# 04_ADC.net
KiCad netlist of a schematic drawn in Altium Designer
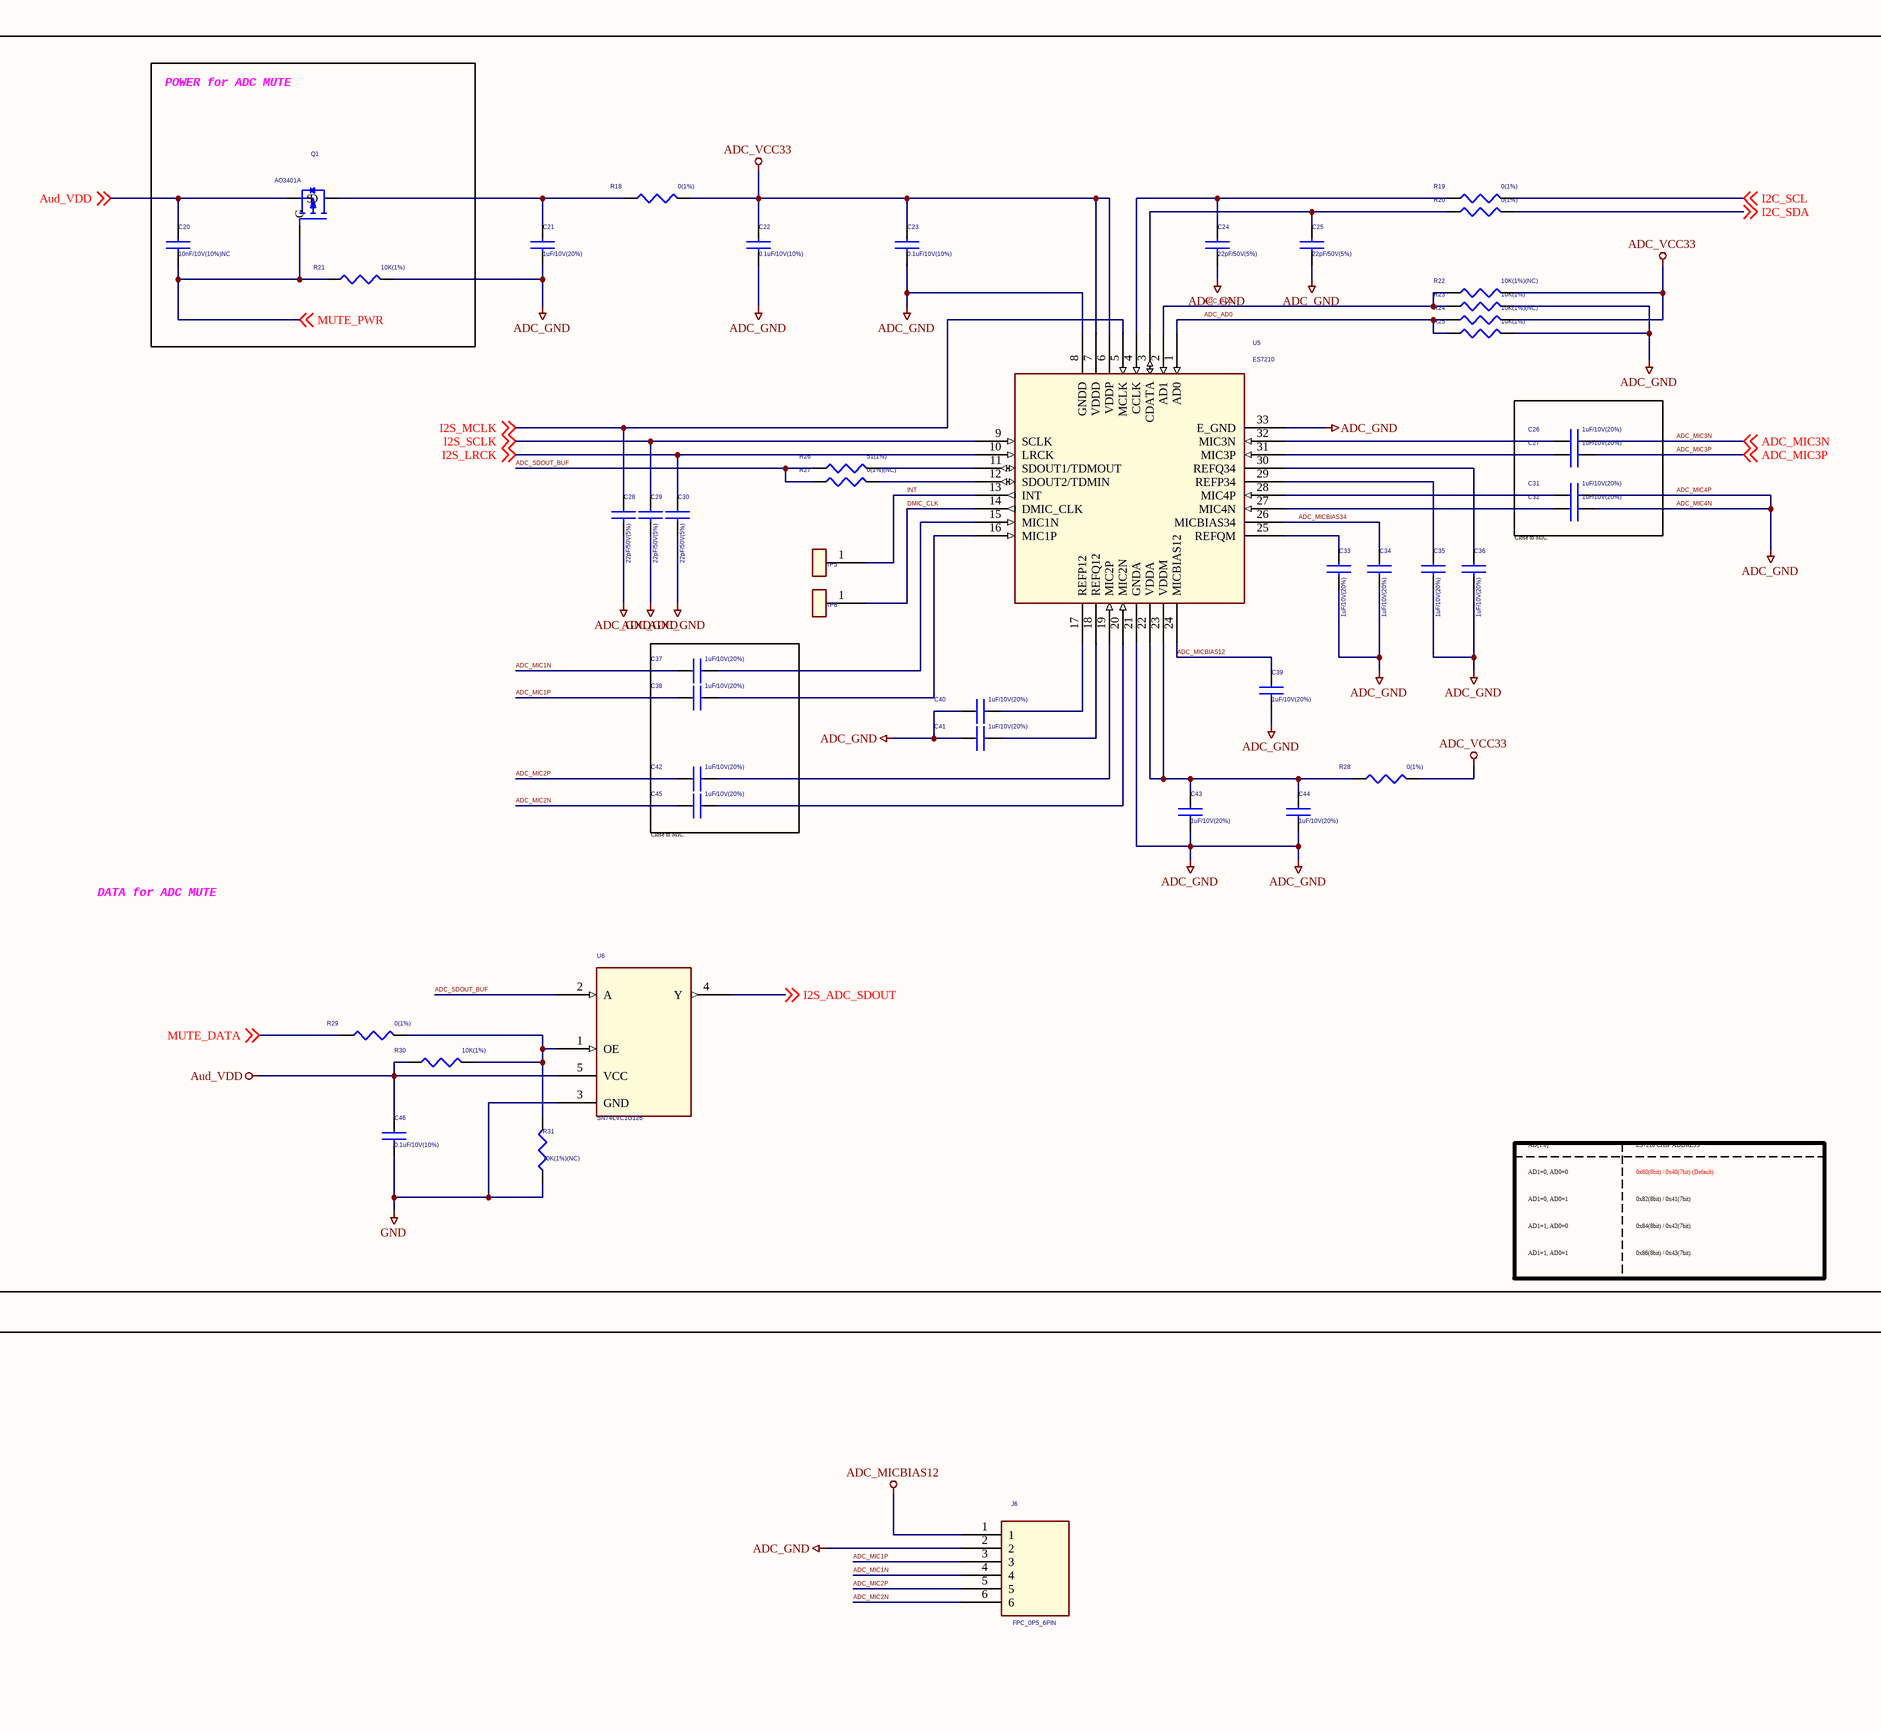
[diagram p0: 04_ADC.SchDoc, left]
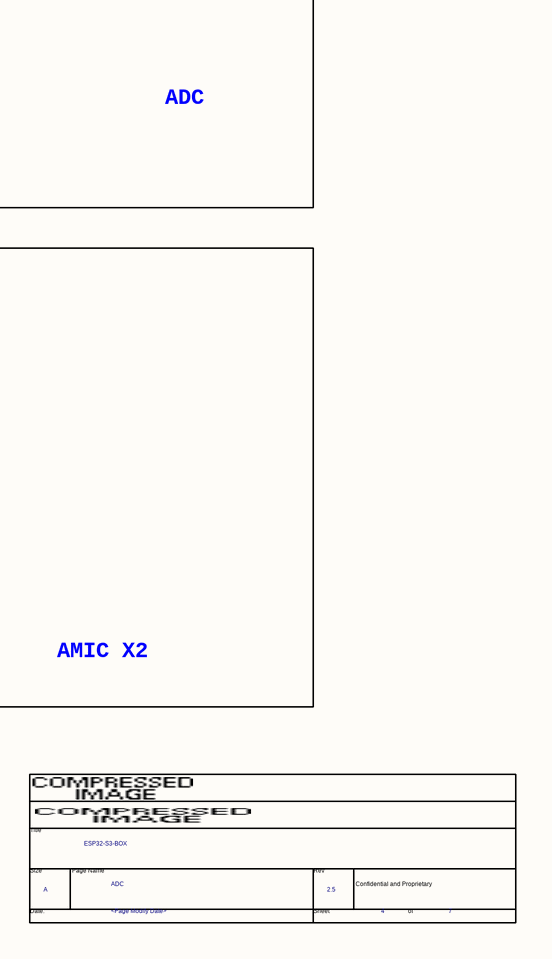
[diagram p1: 04_ADC.SchDoc, right]

(export (version "E")
  (design (tool "Eeschema 10.0.6"))
  (components
    (comp (ref "*")
      (value "espTitleBlock3")
      (fields
        (field (name "PAGE MODIFY DATE") "<Page Modify Date>")
        (field (name "PAGE NAME") "ADC")
        (field (name "TITLE") "ESP32-S3-BOX")
        (field (name "PAGE SIZE") "A")
        (field (name "PAGE NUMBER") "4")
        (field (name "PAGE COUNT") "7")
        (field (name "REVCODE") "2.5")
      )
      (libsource (lib "*") (part "espTitleBlock3"))
    )
    (comp (ref "C20")
      (value "10nF/10V(10%)NC")
      (footprint "C0201")
      (fields (field (name "PART NUMBER") "ES11024103600000"))
      (libsource (lib "*") (part "CAPACITOR"))
    )
    (comp (ref "C21")
      (value "1uF/10V(20%)")
      (footprint "C0201")
      (fields (field (name "PART NUMBER") "ES11026103700001"))
      (libsource (lib "*") (part "CAPACITOR"))
    )
    (comp (ref "C22")
      (value "0.1uF/10V(10%)")
      (footprint "C0201")
      (fields (field (name "PART NUMBER") "ES11025103610001"))
      (libsource (lib "*") (part "CAPACITOR"))
    )
    (comp (ref "C23")
      (value "0.1uF/10V(10%)")
      (footprint "C0201")
      (fields (field (name "PART NUMBER") "ES11025103610001"))
      (libsource (lib "*") (part "CAPACITOR"))
    )
    (comp (ref "C24")
      (value "22pF/50V(5%)")
      (footprint "C0201")
      (fields (field (name "PART NUMBER") "ES11021226520000"))
      (libsource (lib "*") (part "CAPACITOR"))
    )
    (comp (ref "C25")
      (value "22pF/50V(5%)")
      (footprint "C0201")
      (fields (field (name "PART NUMBER") "ES11021226520000"))
      (libsource (lib "*") (part "CAPACITOR"))
    )
    (comp (ref "C26")
      (value "1uF/10V(20%)")
      (footprint "C0201")
      (fields (field (name "PART NUMBER") "ES11026103700001"))
      (libsource (lib "*") (part "CAPACITOR"))
    )
    (comp (ref "C27")
      (value "1uF/10V(20%)")
      (footprint "C0201")
      (fields (field (name "PART NUMBER") "ES11026103700001"))
      (libsource (lib "*") (part "CAPACITOR"))
    )
    (comp (ref "C28")
      (value "22pF/50V(5%)")
      (footprint "C0201")
      (fields (field (name "PART NUMBER") "ES11021226520000"))
      (libsource (lib "*") (part "CAPACITOR"))
    )
    (comp (ref "C29")
      (value "22pF/50V(5%)")
      (footprint "C0201")
      (fields (field (name "PART NUMBER") "ES11021226520000"))
      (libsource (lib "*") (part "CAPACITOR"))
    )
    (comp (ref "C30")
      (value "22pF/50V(5%)")
      (footprint "C0201")
      (fields (field (name "PART NUMBER") "ES11021226520000"))
      (libsource (lib "*") (part "CAPACITOR"))
    )
    (comp (ref "C31")
      (value "1uF/10V(20%)")
      (footprint "C0201")
      (fields (field (name "PART NUMBER") "ES11026103700001"))
      (libsource (lib "*") (part "CAPACITOR"))
    )
    (comp (ref "C32")
      (value "1uF/10V(20%)")
      (footprint "C0201")
      (fields (field (name "PART NUMBER") "ES11026103700001"))
      (libsource (lib "*") (part "CAPACITOR"))
    )
    (comp (ref "C33")
      (value "1uF/10V(20%)")
      (footprint "C0201")
      (fields (field (name "PART NUMBER") "ES11026103700001"))
      (libsource (lib "*") (part "CAPACITOR"))
    )
    (comp (ref "C34")
      (value "1uF/10V(20%)")
      (footprint "C0201")
      (fields (field (name "PART NUMBER") "ES11026103700001"))
      (libsource (lib "*") (part "CAPACITOR"))
    )
    (comp (ref "C35")
      (value "1uF/10V(20%)")
      (footprint "C0201")
      (fields (field (name "PART NUMBER") "ES11026103700001"))
      (libsource (lib "*") (part "CAPACITOR"))
    )
    (comp (ref "C36")
      (value "1uF/10V(20%)")
      (footprint "C0201")
      (fields (field (name "PART NUMBER") "ES11026103700001"))
      (libsource (lib "*") (part "CAPACITOR"))
    )
    (comp (ref "C37")
      (value "1uF/10V(20%)")
      (footprint "C0201")
      (fields (field (name "PART NUMBER") "ES11026103700001"))
      (libsource (lib "*") (part "CAPACITOR"))
    )
    (comp (ref "C38")
      (value "1uF/10V(20%)")
      (footprint "C0201")
      (fields (field (name "PART NUMBER") "ES11026103700001"))
      (libsource (lib "*") (part "CAPACITOR"))
    )
    (comp (ref "C39")
      (value "1uF/10V(20%)")
      (footprint "C0201")
      (fields (field (name "PART NUMBER") "ES11026103700001"))
      (libsource (lib "*") (part "CAPACITOR"))
    )
    (comp (ref "C40")
      (value "1uF/10V(20%)")
      (footprint "C0201")
      (fields (field (name "PART NUMBER") "ES11026103700001"))
      (libsource (lib "*") (part "CAPACITOR"))
    )
    (comp (ref "C41")
      (value "1uF/10V(20%)")
      (footprint "C0201")
      (fields (field (name "PART NUMBER") "ES11026103700001"))
      (libsource (lib "*") (part "CAPACITOR"))
    )
    (comp (ref "C42")
      (value "1uF/10V(20%)")
      (footprint "C0201")
      (fields (field (name "PART NUMBER") "ES11026103700001"))
      (libsource (lib "*") (part "CAPACITOR"))
    )
    (comp (ref "C43")
      (value "1uF/10V(20%)")
      (footprint "C0201")
      (fields (field (name "PART NUMBER") "ES11026103700001"))
      (libsource (lib "*") (part "CAPACITOR"))
    )
    (comp (ref "C44")
      (value "1uF/10V(20%)")
      (footprint "C0201")
      (fields (field (name "PART NUMBER") "ES11026103700001"))
      (libsource (lib "*") (part "CAPACITOR"))
    )
    (comp (ref "C45")
      (value "1uF/10V(20%)")
      (footprint "C0201")
      (fields (field (name "PART NUMBER") "ES11026103700001"))
      (libsource (lib "*") (part "CAPACITOR"))
    )
    (comp (ref "C46")
      (value "0.1uF/10V(10%)")
      (footprint "C0201")
      (fields (field (name "PART NUMBER") "ES11025103610001"))
      (libsource (lib "*") (part "CAPACITOR"))
    )
    (comp (ref "J6")
      (value "FPC_0P5_6PIN")
      (footprint "FPC_0P5_6PIN")
      (libsource (lib "*") (part "FPC_0P5_6PIN"))
    )
    (comp (ref "Q1")
      (value "AO3401A")
      (footprint "SOT23-3")
      (fields (field (name "PART NUMBER") "ES31460000000000"))
      (libsource (lib "*") (part "PMOS"))
    )
    (comp (ref "R18")
      (value "0(1%)")
      (footprint "R0402")
      (fields (field (name "PART NUMBER") "ES21040000000001"))
      (libsource (lib "*") (part "RESISTOR"))
    )
    (comp (ref "R19")
      (value "0(1%)")
      (footprint "R0201")
      (fields (field (name "PART NUMBER") "ES21020000000001"))
      (libsource (lib "*") (part "RESISTOR"))
    )
    (comp (ref "R20")
      (value "0(1%)")
      (footprint "R0201")
      (fields (field (name "PART NUMBER") "ES21020000000001"))
      (libsource (lib "*") (part "RESISTOR"))
    )
    (comp (ref "R21")
      (value "10K(1%)")
      (footprint "R0201")
      (fields (field (name "PART NUMBER") "ES21024100000001"))
      (libsource (lib "*") (part "RESISTOR"))
    )
    (comp (ref "R22")
      (value "10K(1%)(NC)")
      (footprint "R0201")
      (fields (field (name "PART NUMBER") "ES21024100000001"))
      (libsource (lib "*") (part "RESISTOR"))
    )
    (comp (ref "R23")
      (value "10K(1%)")
      (footprint "R0201")
      (fields (field (name "PART NUMBER") "ES21024100000001"))
      (libsource (lib "*") (part "RESISTOR"))
    )
    (comp (ref "R24")
      (value "10K(1%)(NC)")
      (footprint "R0201")
      (fields (field (name "PART NUMBER") "ES21024100000001"))
      (libsource (lib "*") (part "RESISTOR"))
    )
    (comp (ref "R25")
      (value "10K(1%)")
      (footprint "R0201")
      (fields (field (name "PART NUMBER") "ES21024100000001"))
      (libsource (lib "*") (part "RESISTOR"))
    )
    (comp (ref "R26")
      (value "51(1%)")
      (footprint "R0201")
      (fields (field (name "PART NUMBER") "ES21021510000001"))
      (libsource (lib "*") (part "RESISTOR"))
    )
    (comp (ref "R27")
      (value "0(1%)(NC)")
      (footprint "R0201")
      (fields (field (name "PART NUMBER") "ES21020000000001"))
      (libsource (lib "*") (part "RESISTOR"))
    )
    (comp (ref "R28")
      (value "0(1%)")
      (footprint "R0402")
      (fields (field (name "PART NUMBER") "ES21040000000001"))
      (libsource (lib "*") (part "RESISTOR"))
    )
    (comp (ref "R29")
      (value "0(1%)")
      (footprint "R0201")
      (fields (field (name "PART NUMBER") "ES21020000000001"))
      (libsource (lib "*") (part "RESISTOR"))
    )
    (comp (ref "R30")
      (value "10K(1%)")
      (footprint "R0201")
      (fields (field (name "PART NUMBER") "ES21024100000001"))
      (libsource (lib "*") (part "RESISTOR"))
    )
    (comp (ref "R31")
      (value "10K(1%)(NC)")
      (footprint "R0201")
      (fields (field (name "PART NUMBER") "ES21024100000001"))
      (libsource (lib "*") (part "RESISTOR"))
    )
    (comp (ref "TP5")
      (value "TESTPOINT")
      (footprint "TPC_D40")
      (fields (field (name "PART NUMBER") "ES51990010000000"))
      (libsource (lib "*") (part "TESTPOINT"))
    )
    (comp (ref "TP6")
      (value "TESTPOINT")
      (footprint "TPC_D40")
      (fields (field (name "PART NUMBER") "ES51990010000000"))
      (libsource (lib "*") (part "TESTPOINT"))
    )
    (comp (ref "U5")
      (value "ES7210")
      (footprint "QFN32_0P4_4")
      (fields (field (name "PART NUMBER") "ES41181401000000"))
      (libsource (lib "*") (part "ES7210"))
    )
    (comp (ref "U6") (value "SN74LVC1G126") (footprint "SC70-5") (libsource (lib "*") (part "SN74LVC1G126")))
  )
  (nets
    (net (code "1") (name "/ADC_AD0") (class "Default")
      (node (ref "R24") (pin "1") (pinfunction "1_1") (pintype "passive"))
      (node (ref "R25") (pin "1") (pinfunction "1_1") (pintype "passive"))
      (node (ref "U5") (pin "1") (pinfunction "AD0_1") (pintype "input"))
    )
    (net (code "2") (name "/ADC_AD1") (class "Default")
      (node (ref "R22") (pin "1") (pinfunction "1_1") (pintype "passive"))
      (node (ref "R23") (pin "1") (pinfunction "1_1") (pintype "passive"))
      (node (ref "U5") (pin "2") (pinfunction "AD1_2") (pintype "input"))
    )
    (net (code "3") (name "/ADC_MIC1N") (class "Default")
      (node (ref "C37") (pin "1") (pinfunction "1_1") (pintype "passive"))
      (node (ref "J6") (pin "4") (pinfunction "4_4") (pintype "passive"))
    )
    (net (code "4") (name "/ADC_MIC1P") (class "Default")
      (node (ref "C38") (pin "1") (pinfunction "1_1") (pintype "passive"))
      (node (ref "J6") (pin "3") (pinfunction "3_3") (pintype "passive"))
    )
    (net (code "5") (name "/ADC_MIC2N") (class "Default")
      (node (ref "C45") (pin "1") (pinfunction "1_1") (pintype "passive"))
      (node (ref "J6") (pin "6") (pinfunction "6_6") (pintype "passive"))
    )
    (net (code "6") (name "/ADC_MIC2P") (class "Default")
      (node (ref "C42") (pin "1") (pinfunction "1_1") (pintype "passive"))
      (node (ref "J6") (pin "5") (pinfunction "5_5") (pintype "passive"))
    )
    (net (code "7") (name "/ADC_MICBIAS34") (class "Default")
      (node (ref "C34") (pin "1") (pinfunction "1_1") (pintype "passive"))
      (node (ref "U5") (pin "26") (pinfunction "MICBIAS34_26") (pintype "power_in"))
    )
    (net (code "8") (name "/ADC_SDOUT_BUF") (class "Default")
      (node (ref "R26") (pin "1") (pinfunction "1_1") (pintype "passive"))
      (node (ref "R27") (pin "1") (pinfunction "1_1") (pintype "passive"))
      (node (ref "U6") (pin "2") (pinfunction "A_2") (pintype "input"))
    )
    (net (code "9") (name "/DMIC_CLK") (class "Default")
      (node (ref "TP6") (pin "1") (pinfunction "1_1") (pintype "passive"))
      (node (ref "U5") (pin "14") (pinfunction "DMIC_CLK_14") (pintype "output"))
    )
    (net (code "10") (name "/INT") (class "Default")
      (node (ref "TP5") (pin "1") (pinfunction "1_1") (pintype "passive"))
      (node (ref "U5") (pin "13") (pinfunction "INT_13") (pintype "output"))
    )
    (net (code "11") (name "ADC_GND") (class "Default")
      (node (ref "C21") (pin "2") (pinfunction "2_2") (pintype "passive"))
      (node (ref "C22") (pin "2") (pinfunction "2_2") (pintype "passive"))
      (node (ref "C23") (pin "2") (pinfunction "2_2") (pintype "passive"))
      (node (ref "C24") (pin "2") (pinfunction "2_2") (pintype "passive"))
      (node (ref "C25") (pin "2") (pinfunction "2_2") (pintype "passive"))
      (node (ref "C28") (pin "2") (pinfunction "2_2") (pintype "passive"))
      (node (ref "C29") (pin "2") (pinfunction "2_2") (pintype "passive"))
      (node (ref "C30") (pin "2") (pinfunction "2_2") (pintype "passive"))
      (node (ref "C31") (pin "2") (pinfunction "2_2") (pintype "passive"))
      (node (ref "C32") (pin "2") (pinfunction "2_2") (pintype "passive"))
      (node (ref "C33") (pin "2") (pinfunction "2_2") (pintype "passive"))
      (node (ref "C34") (pin "2") (pinfunction "2_2") (pintype "passive"))
      (node (ref "C35") (pin "2") (pinfunction "2_2") (pintype "passive"))
      (node (ref "C36") (pin "2") (pinfunction "2_2") (pintype "passive"))
      (node (ref "C39") (pin "2") (pinfunction "2_2") (pintype "passive"))
      (node (ref "C40") (pin "1") (pinfunction "1_1") (pintype "passive"))
      (node (ref "C41") (pin "1") (pinfunction "1_1") (pintype "passive"))
      (node (ref "C43") (pin "2") (pinfunction "2_2") (pintype "passive"))
      (node (ref "C44") (pin "2") (pinfunction "2_2") (pintype "passive"))
      (node (ref "J6") (pin "2") (pinfunction "2_2") (pintype "passive"))
      (node (ref "R21") (pin "2") (pinfunction "2_2") (pintype "passive"))
      (node (ref "R23") (pin "2") (pinfunction "2_2") (pintype "passive"))
      (node (ref "R25") (pin "2") (pinfunction "2_2") (pintype "passive"))
      (node (ref "U5") (pin "21") (pinfunction "GNDA_21") (pintype "power_in"))
      (node (ref "U5") (pin "33") (pinfunction "E_GND_33") (pintype "power_in"))
      (node (ref "U5") (pin "8") (pinfunction "GNDD_8") (pintype "power_in"))
    )
    (net (code "12") (name "ADC_MIC3N") (class "Default")
      (node (ref "C26") (pin "2") (pinfunction "2_2") (pintype "passive"))
    )
    (net (code "13") (name "ADC_MIC3P") (class "Default")
      (node (ref "C27") (pin "2") (pinfunction "2_2") (pintype "passive"))
    )
    (net (code "14") (name "ADC_MICBIAS12") (class "Default")
      (node (ref "C39") (pin "1") (pinfunction "1_1") (pintype "passive"))
      (node (ref "J6") (pin "1") (pinfunction "1_1") (pintype "passive"))
      (node (ref "U5") (pin "24") (pinfunction "MICBIAS12_24") (pintype "power_in"))
    )
    (net (code "15") (name "ADC_VCC33") (class "Default")
      (node (ref "C22") (pin "1") (pinfunction "1_1") (pintype "passive"))
      (node (ref "C23") (pin "1") (pinfunction "1_1") (pintype "passive"))
      (node (ref "R18") (pin "2") (pinfunction "2_2") (pintype "passive"))
      (node (ref "R22") (pin "2") (pinfunction "2_2") (pintype "passive"))
      (node (ref "R24") (pin "2") (pinfunction "2_2") (pintype "passive"))
      (node (ref "R28") (pin "2") (pinfunction "2_2") (pintype "passive"))
      (node (ref "U5") (pin "6") (pinfunction "VDDP_6") (pintype "power_in"))
      (node (ref "U5") (pin "7") (pinfunction "VDDD_7") (pintype "power_in"))
    )
    (net (code "16") (name "Aud_VDD") (class "Default")
      (node (ref "C20") (pin "1") (pinfunction "1_1") (pintype "passive"))
      (node (ref "C46") (pin "1") (pinfunction "1_1") (pintype "passive"))
      (node (ref "Q1") (pin "2") (pinfunction "S_2") (pintype "passive"))
      (node (ref "R30") (pin "1") (pinfunction "1_1") (pintype "passive"))
      (node (ref "U6") (pin "5") (pinfunction "VCC_5") (pintype "power_in"))
    )
    (net (code "17") (name "GND") (class "Default")
      (node (ref "C46") (pin "2") (pinfunction "2_2") (pintype "passive"))
      (node (ref "R31") (pin "1") (pinfunction "1_1") (pintype "passive"))
      (node (ref "U6") (pin "3") (pinfunction "GND_3") (pintype "power_in"))
    )
    (net (code "18") (name "I2C_SCL") (class "Default")
      (node (ref "R19") (pin "2") (pinfunction "2_2") (pintype "passive"))
    )
    (net (code "19") (name "I2C_SDA") (class "Default")
      (node (ref "R20") (pin "2") (pinfunction "2_2") (pintype "passive"))
    )
    (net (code "20") (name "I2S_ADC_SDOUT") (class "Default")
      (node (ref "U6") (pin "4") (pinfunction "Y_4") (pintype "output"))
    )
    (net (code "21") (name "I2S_LRCK") (class "Default")
      (node (ref "C30") (pin "1") (pinfunction "1_1") (pintype "passive"))
      (node (ref "U5") (pin "10") (pinfunction "LRCK_10") (pintype "input"))
    )
    (net (code "22") (name "I2S_MCLK") (class "Default")
      (node (ref "C28") (pin "1") (pinfunction "1_1") (pintype "passive"))
      (node (ref "U5") (pin "5") (pinfunction "MCLK_5") (pintype "input"))
    )
    (net (code "23") (name "I2S_SCLK") (class "Default")
      (node (ref "C29") (pin "1") (pinfunction "1_1") (pintype "passive"))
      (node (ref "U5") (pin "9") (pinfunction "SCLK_9") (pintype "input"))
    )
    (net (code "24") (name "MUTE_DATA") (class "Default")
      (node (ref "R29") (pin "1") (pinfunction "1_1") (pintype "passive"))
    )
    (net (code "25") (name "MUTE_PWR") (class "Default")
      (node (ref "C20") (pin "2") (pinfunction "2_2") (pintype "passive"))
      (node (ref "Q1") (pin "1") (pinfunction "G_1") (pintype "passive"))
      (node (ref "R21") (pin "1") (pinfunction "1_1") (pintype "passive"))
    )
    (net (code "26") (name "Net-(Q1-D)") (class "Default")
      (node (ref "C21") (pin "1") (pinfunction "1_1") (pintype "passive"))
      (node (ref "Q1") (pin "3") (pinfunction "D_3") (pintype "passive"))
      (node (ref "R18") (pin "1") (pinfunction "1_1") (pintype "passive"))
    )
    (net (code "27") (name "Net-(U5-CCLK)") (class "Default")
      (node (ref "C24") (pin "1") (pinfunction "1_1") (pintype "passive"))
      (node (ref "R19") (pin "1") (pinfunction "1_1") (pintype "passive"))
      (node (ref "U5") (pin "4") (pinfunction "CCLK_4") (pintype "input"))
    )
    (net (code "28") (name "Net-(U5-CDATA)") (class "Default")
      (node (ref "C25") (pin "1") (pinfunction "1_1") (pintype "passive"))
      (node (ref "R20") (pin "1") (pinfunction "1_1") (pintype "passive"))
      (node (ref "U5") (pin "3") (pinfunction "CDATA_3") (pintype "bidirectional"))
    )
    (net (code "29") (name "Net-(U5-MIC1N)") (class "Default")
      (node (ref "C37") (pin "2") (pinfunction "2_2") (pintype "passive"))
      (node (ref "U5") (pin "15") (pinfunction "MIC1N_15") (pintype "input"))
    )
    (net (code "30") (name "Net-(U5-MIC1P)") (class "Default")
      (node (ref "C38") (pin "2") (pinfunction "2_2") (pintype "passive"))
      (node (ref "U5") (pin "16") (pinfunction "MIC1P_16") (pintype "input"))
    )
    (net (code "31") (name "Net-(U5-MIC2N)") (class "Default")
      (node (ref "C45") (pin "2") (pinfunction "2_2") (pintype "passive"))
      (node (ref "U5") (pin "20") (pinfunction "MIC2N_20") (pintype "input"))
    )
    (net (code "32") (name "Net-(U5-MIC2P)") (class "Default")
      (node (ref "C42") (pin "2") (pinfunction "2_2") (pintype "passive"))
      (node (ref "U5") (pin "19") (pinfunction "MIC2P_19") (pintype "input"))
    )
    (net (code "33") (name "Net-(U5-MIC3N)") (class "Default")
      (node (ref "C26") (pin "1") (pinfunction "1_1") (pintype "passive"))
      (node (ref "U5") (pin "32") (pinfunction "MIC3N_32") (pintype "input"))
    )
    (net (code "34") (name "Net-(U5-MIC3P)") (class "Default")
      (node (ref "C27") (pin "1") (pinfunction "1_1") (pintype "passive"))
      (node (ref "U5") (pin "31") (pinfunction "MIC3P_31") (pintype "input"))
    )
    (net (code "35") (name "Net-(U5-MIC4N)") (class "Default")
      (node (ref "C32") (pin "1") (pinfunction "1_1") (pintype "passive"))
      (node (ref "U5") (pin "27") (pinfunction "MIC4N_27") (pintype "input"))
    )
    (net (code "36") (name "Net-(U5-MIC4P)") (class "Default")
      (node (ref "C31") (pin "1") (pinfunction "1_1") (pintype "passive"))
      (node (ref "U5") (pin "28") (pinfunction "MIC4P_28") (pintype "input"))
    )
    (net (code "37") (name "Net-(U5-REFP12)") (class "Default")
      (node (ref "C40") (pin "2") (pinfunction "2_2") (pintype "passive"))
      (node (ref "U5") (pin "17") (pinfunction "REFP12_17") (pintype "power_in"))
    )
    (net (code "38") (name "Net-(U5-REFP34)") (class "Default")
      (node (ref "C35") (pin "1") (pinfunction "1_1") (pintype "passive"))
      (node (ref "U5") (pin "29") (pinfunction "REFP34_29") (pintype "power_in"))
    )
    (net (code "39") (name "Net-(U5-REFQ12)") (class "Default")
      (node (ref "C41") (pin "2") (pinfunction "2_2") (pintype "passive"))
      (node (ref "U5") (pin "18") (pinfunction "REFQ12_18") (pintype "power_in"))
    )
    (net (code "40") (name "Net-(U5-REFQ34)") (class "Default")
      (node (ref "C36") (pin "1") (pinfunction "1_1") (pintype "passive"))
      (node (ref "U5") (pin "30") (pinfunction "REFQ34_30") (pintype "power_in"))
    )
    (net (code "41") (name "Net-(U5-REFQM)") (class "Default")
      (node (ref "C33") (pin "1") (pinfunction "1_1") (pintype "passive"))
      (node (ref "U5") (pin "25") (pinfunction "REFQM_25") (pintype "power_in"))
    )
    (net (code "42") (name "Net-(U5-SDOUT1{slash}TDMOUT)") (class "Default")
      (node (ref "R26") (pin "2") (pinfunction "2_2") (pintype "passive"))
      (node (ref "U5") (pin "11") (pinfunction "SDOUT1/TDMOUT_11") (pintype "bidirectional"))
    )
    (net (code "43") (name "Net-(U5-SDOUT2{slash}TDMIN)") (class "Default")
      (node (ref "R27") (pin "2") (pinfunction "2_2") (pintype "passive"))
      (node (ref "U5") (pin "12") (pinfunction "SDOUT2/TDMIN_12") (pintype "bidirectional"))
    )
    (net (code "44") (name "Net-(U5-VDDA)") (class "Default")
      (node (ref "C43") (pin "1") (pinfunction "1_1") (pintype "passive"))
      (node (ref "C44") (pin "1") (pinfunction "1_1") (pintype "passive"))
      (node (ref "R28") (pin "1") (pinfunction "1_1") (pintype "passive"))
      (node (ref "U5") (pin "22") (pinfunction "VDDA_22") (pintype "power_in"))
      (node (ref "U5") (pin "23") (pinfunction "VDDM_23") (pintype "power_in"))
    )
    (net (code "45") (name "Net-(U6-OE)") (class "Default")
      (node (ref "R29") (pin "2") (pinfunction "2_2") (pintype "passive"))
      (node (ref "R30") (pin "2") (pinfunction "2_2") (pintype "passive"))
      (node (ref "R31") (pin "2") (pinfunction "2_2") (pintype "passive"))
      (node (ref "U6") (pin "1") (pinfunction "OE_1") (pintype "input"))
    )
  )
)
